# power_dist.net
KiCad netlist of a schematic drawn in EAGLE
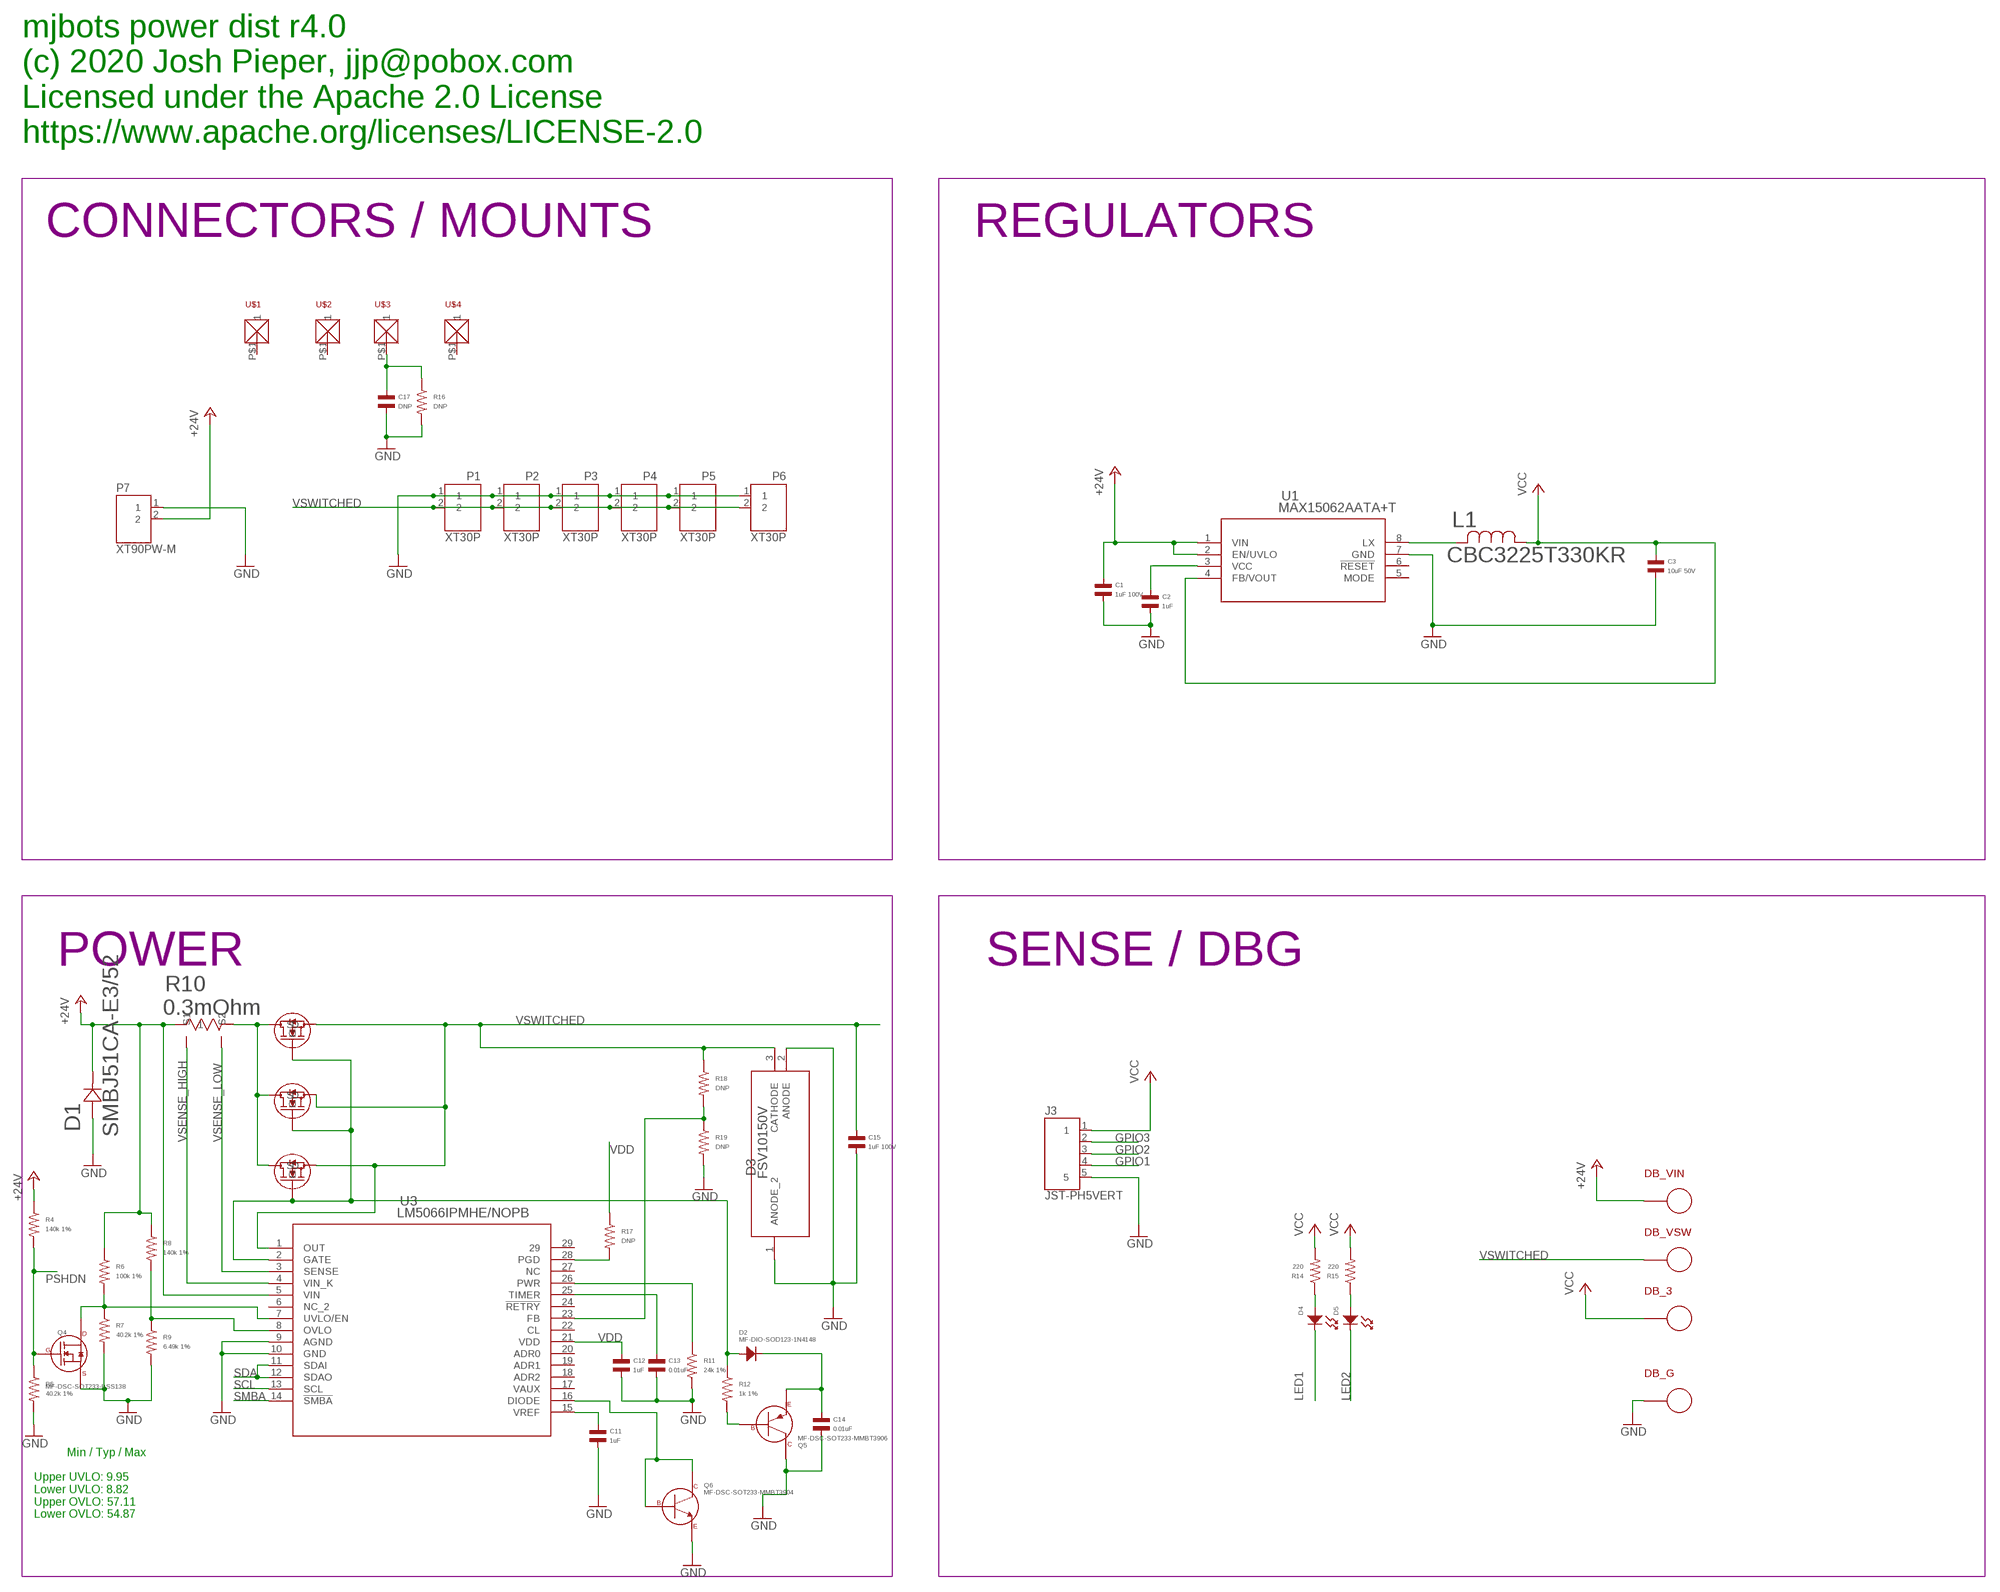
[diagram p0: schematic, sheet 1, part 1 of 2]
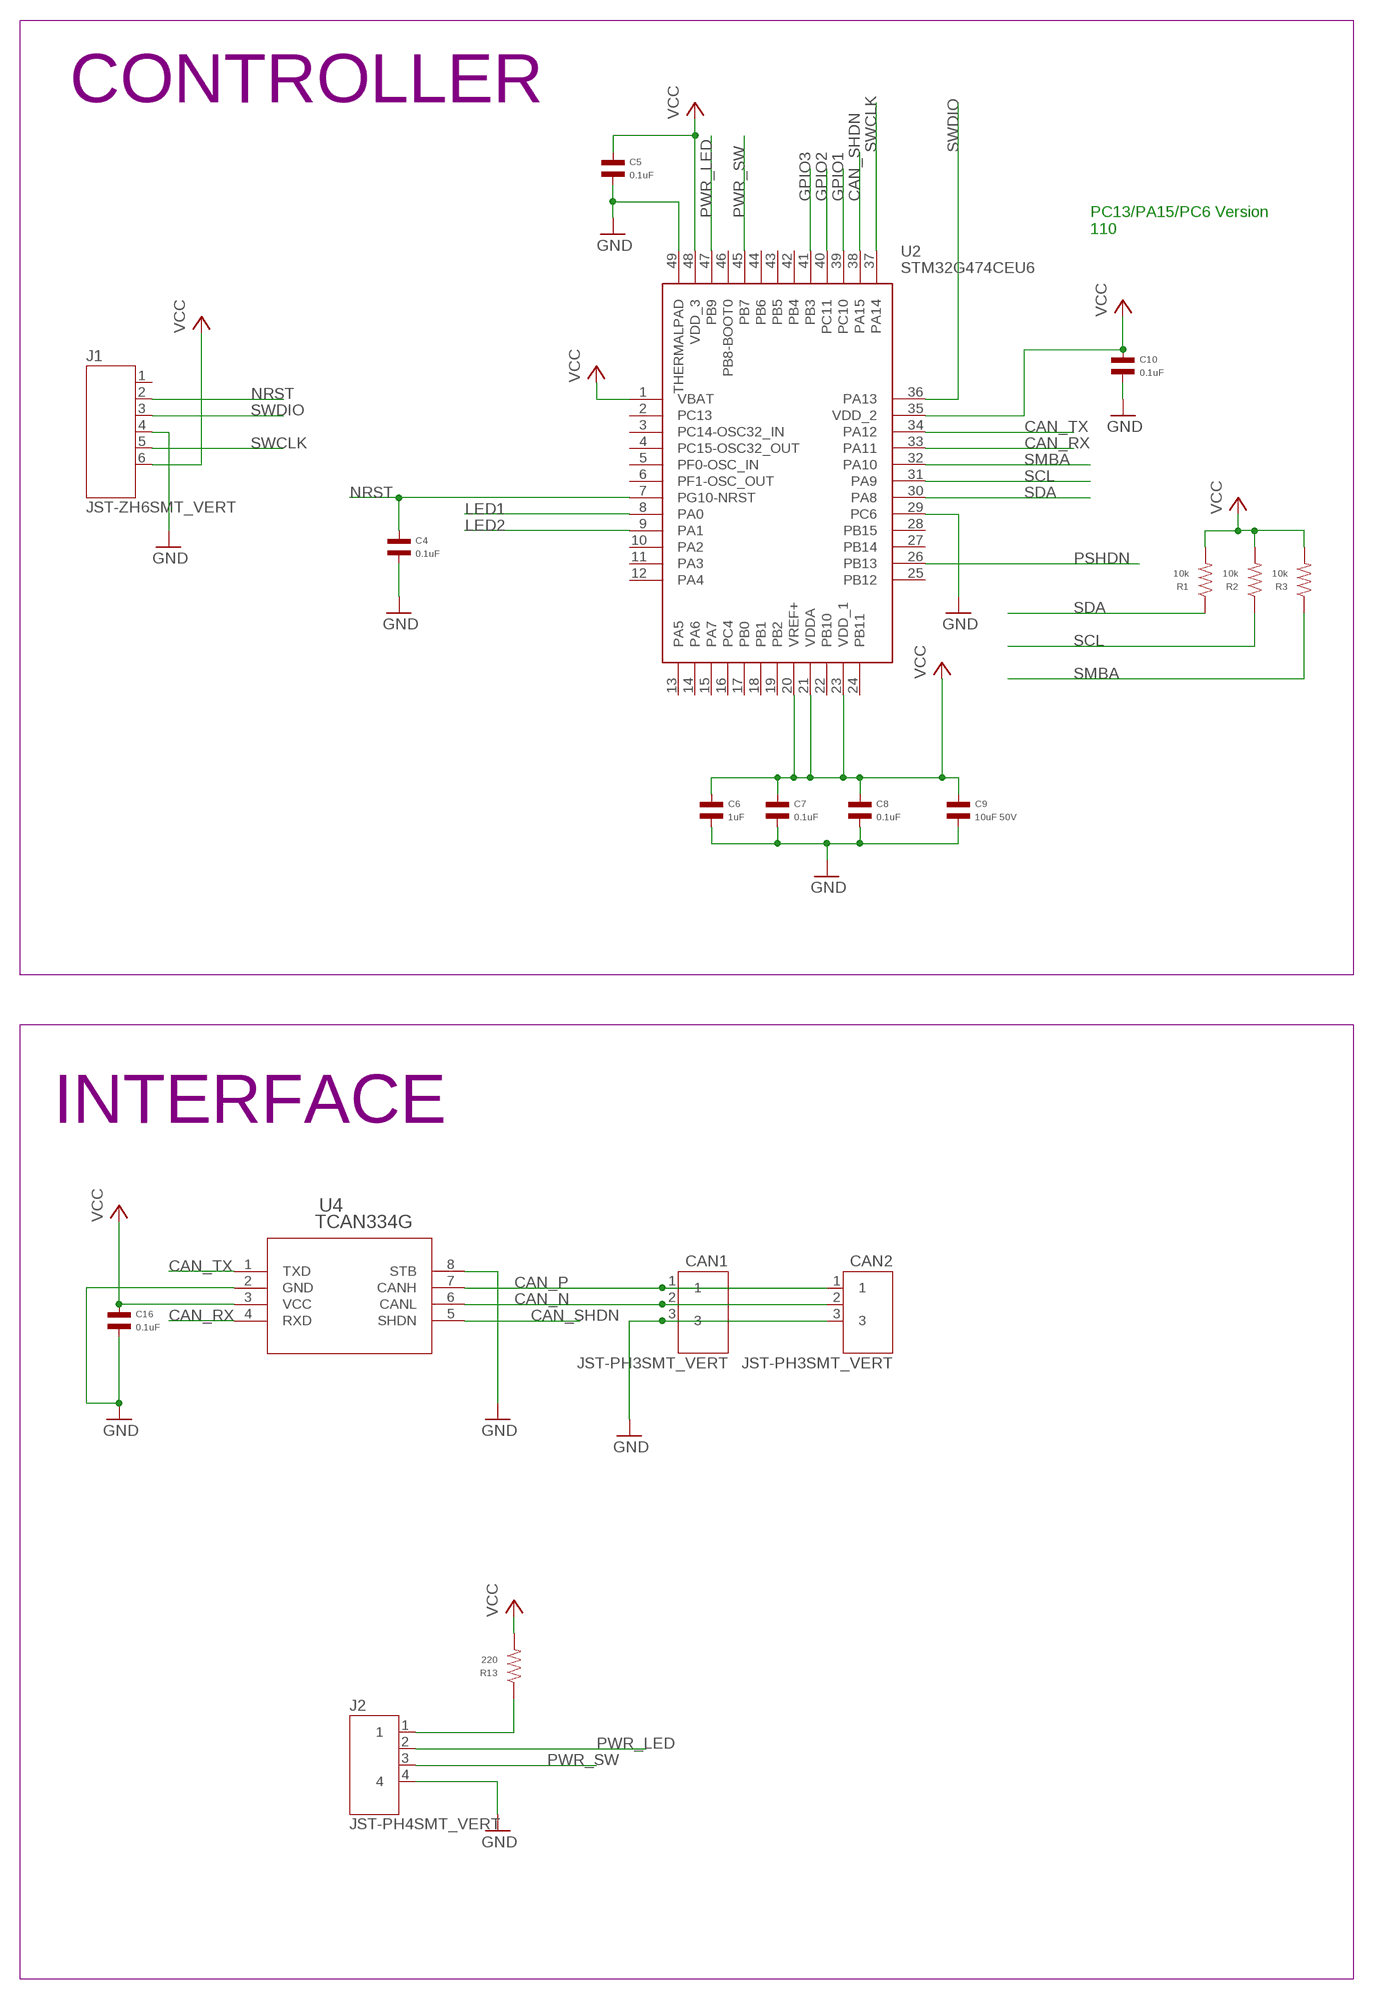
[diagram p1: schematic, sheet 1, part 2 of 2]

(export (version "E")
  (design (tool "Eeschema 10.0.6"))
  (components
    (comp (ref "C1")
      (value "1uF 100V")
      (footprint "eagle-import:C0805")
      (fields (field (name "MF") "MURATA") (field (name "MPN") "GCM21BC72A105KE36L"))
      (libsource (lib "eagle-import") (part "CAPACITOR_NP_0805"))
    )
    (comp (ref "C2")
      (value "1uF")
      (footprint "eagle-import:C0603")
      (fields (field (name "HOUSEPART") "1") (field (name "MPN") "MF-CAP-0603-1uF"))
      (libsource (lib "eagle-import") (part "CAPACITOR_NP_0603"))
    )
    (comp (ref "C3")
      (value "10uF 50V")
      (footprint "eagle-import:C1206")
      (fields (field (name "MF") "TDK") (field (name "MPN") "C3216X7R1H106K160AE"))
      (libsource (lib "eagle-import") (part "CAPACITOR_NP_1206"))
    )
    (comp (ref "C4")
      (value "0.1uF")
      (footprint "eagle-import:C0603")
      (fields (field (name "HOUSEPART") "1") (field (name "MPN") "MF-CAP-0603-0.1uF"))
      (libsource (lib "eagle-import") (part "CAPACITOR_NP_0603"))
    )
    (comp (ref "C5")
      (value "0.1uF")
      (footprint "eagle-import:C0603")
      (fields (field (name "HOUSEPART") "1") (field (name "MPN") "MF-CAP-0603-0.1uF"))
      (libsource (lib "eagle-import") (part "CAPACITOR_NP_0603"))
    )
    (comp (ref "C6")
      (value "1uF")
      (footprint "eagle-import:C0603")
      (fields (field (name "HOUSEPART") "1") (field (name "MPN") "MF-CAP-0603-1uF"))
      (libsource (lib "eagle-import") (part "CAPACITOR_NP_0603"))
    )
    (comp (ref "C7")
      (value "0.1uF")
      (footprint "eagle-import:C0603")
      (fields (field (name "HOUSEPART") "1") (field (name "MPN") "MF-CAP-0603-0.1uF"))
      (libsource (lib "eagle-import") (part "CAPACITOR_NP_0603"))
    )
    (comp (ref "C8")
      (value "0.1uF")
      (footprint "eagle-import:C0603")
      (fields (field (name "HOUSEPART") "1") (field (name "MPN") "MF-CAP-0603-0.1uF"))
      (libsource (lib "eagle-import") (part "CAPACITOR_NP_0603"))
    )
    (comp (ref "C9")
      (value "10uF 50V")
      (footprint "eagle-import:C1206")
      (fields (field (name "MF") "TDK") (field (name "MPN") "C3216X7R1H106K160AE"))
      (libsource (lib "eagle-import") (part "CAPACITOR_NP_1206"))
    )
    (comp (ref "C10")
      (value "0.1uF")
      (footprint "eagle-import:C0603")
      (fields (field (name "HOUSEPART") "1") (field (name "MPN") "MF-CAP-0603-0.1uF"))
      (libsource (lib "eagle-import") (part "CAPACITOR_NP_0603"))
    )
    (comp (ref "C11")
      (value "1uF")
      (footprint "eagle-import:C0603")
      (fields (field (name "HOUSEPART") "1") (field (name "MPN") "MF-CAP-0603-1uF"))
      (libsource (lib "eagle-import") (part "CAPACITOR_NP_0603"))
    )
    (comp (ref "C12")
      (value "1uF")
      (footprint "eagle-import:C0603")
      (fields (field (name "HOUSEPART") "1") (field (name "MPN") "MF-CAP-0603-1uF"))
      (libsource (lib "eagle-import") (part "CAPACITOR_NP_0603"))
    )
    (comp (ref "C13")
      (value "0.01uF")
      (footprint "eagle-import:C0603")
      (fields (field (name "HOUSEPART") "1") (field (name "MPN") "MF-CAP-0603-0.01uF"))
      (libsource (lib "eagle-import") (part "CAPACITOR_NP_0603"))
    )
    (comp (ref "C14")
      (value "0.01uF")
      (footprint "eagle-import:C0603")
      (fields (field (name "HOUSEPART") "1") (field (name "MPN") "MF-CAP-0603-0.01uF"))
      (libsource (lib "eagle-import") (part "CAPACITOR_NP_0603"))
    )
    (comp (ref "C15")
      (value "1uF 100V")
      (footprint "eagle-import:C0805")
      (fields (field (name "MF") "MURATA") (field (name "MPN") "GCM21BC72A105KE36L"))
      (libsource (lib "eagle-import") (part "CAPACITOR_NP_0805"))
    )
    (comp (ref "C16")
      (value "0.1uF")
      (footprint "eagle-import:C0603")
      (fields (field (name "HOUSEPART") "1") (field (name "MPN") "MF-CAP-0603-0.1uF"))
      (libsource (lib "eagle-import") (part "CAPACITOR_NP_0603"))
    )
    (comp (ref "C17")
      (value "DNP")
      (footprint "eagle-import:C0603")
      (fields (field (name "POPULATE") "0"))
      (libsource (lib "eagle-import") (part "CAPACITOR_NP_0603"))
    )
    (comp (ref "CAN1")
      (value "JST-PH3SMT_VERT")
      (footprint "eagle-import:JST_B3B_PH-SM4-TB(LF)(SN)")
      (fields (field (name "MF") "JST") (field (name "MPN") "B3B-PH-SM4-TB(LF)(SN)"))
      (libsource (lib "eagle-import") (part "JST-PH3SMT_VERT"))
    )
    (comp (ref "CAN2")
      (value "JST-PH3SMT_VERT")
      (footprint "eagle-import:JST_B3B_PH-SM4-TB(LF)(SN)")
      (fields (field (name "MF") "JST") (field (name "MPN") "B3B-PH-SM4-TB(LF)(SN)"))
      (libsource (lib "eagle-import") (part "JST-PH3SMT_VERT"))
    )
    (comp (ref "D1")
      (value "SMBJ51CA-E3/52")
      (footprint "eagle-import:DIODE_DO-214AC")
      (libsource (lib "eagle-import") (part "SMBJ51CA-E3/52"))
    )
    (comp (ref "D2")
      (value "MF-DIO-SOD123-1N4148")
      (footprint "eagle-import:SOD-123")
      (fields (field (name "HOUSEPART") "YES") (field (name "HOUSEPART_1") "1"))
      (libsource (lib "eagle-import") (part "DIODES_SOD-123_1N4148"))
    )
    (comp (ref "D3")
      (value "FSV10150V")
      (footprint "eagle-import:TO277-3L_ONS")
      (fields (field (name "COPYRIGHT") "Copyright (C) 2018 Accelerated Designs. All rights reserved"))
      (libsource (lib "eagle-import") (part "FSV10150V"))
    )
    (comp (ref "D4")
      (value "LED_SINGLE-0603")
      (footprint "eagle-import:LED0603")
      (fields
        (field (name "HOUSEPART") "NO")
        (field (name "HOUSEPART_1") "1")
        (field (name "MPN") "MF-LED-0603-RED")
      )
      (libsource (lib "eagle-import") (part "LED_SINGLE-0603"))
    )
    (comp (ref "D5")
      (value "LED_SINGLE-0603")
      (footprint "eagle-import:LED0603")
      (fields
        (field (name "HOUSEPART") "NO")
        (field (name "HOUSEPART_1") "1")
        (field (name "MPN") "MF-LED-0603-RED")
      )
      (libsource (lib "eagle-import") (part "LED_SINGLE-0603"))
    )
    (comp (ref "DB_3")
      (value "PAD24AWG_PAD")
      (footprint "eagle-import:24AWG_PAD")
      (libsource (lib "eagle-import") (part "PAD24AWG_PAD"))
    )
    (comp (ref "DB_G")
      (value "PAD24AWG_PAD")
      (footprint "eagle-import:24AWG_PAD")
      (libsource (lib "eagle-import") (part "PAD24AWG_PAD"))
    )
    (comp (ref "DB_VIN")
      (value "PAD24AWG_PAD")
      (footprint "eagle-import:24AWG_PAD")
      (libsource (lib "eagle-import") (part "PAD24AWG_PAD"))
    )
    (comp (ref "DB_VSW")
      (value "PAD24AWG_PAD")
      (footprint "eagle-import:24AWG_PAD")
      (libsource (lib "eagle-import") (part "PAD24AWG_PAD"))
    )
    (comp (ref "J1")
      (value "JST-ZH6SMT_VERT")
      (footprint "eagle-import:JST_B6B-ZR-SM4-TF(LF)(SN)")
      (fields (field (name "MF") "JST") (field (name "MPN") "B6B-ZR-SM4-TF(LF)(SN)"))
      (libsource (lib "eagle-import") (part "JST-ZH6SMT_VERT"))
    )
    (comp (ref "J2")
      (value "JST-PH4SMT_VERT")
      (footprint "eagle-import:JST_B4B_PH-SM4-TB(LF)(SN)")
      (fields (field (name "MF") "JST") (field (name "MPN") "B4B-PH-SM4-TB(LF)(SN)"))
      (libsource (lib "eagle-import") (part "JST-PH4SMT_VERT"))
    )
    (comp (ref "J3")
      (value "JST-PH5VERT")
      (footprint "eagle-import:JST_B5B_PH-SM4-TB(LF)(SN)")
      (fields (field (name "MF") "JST") (field (name "MPN") "B5B-PH-SM4-TB(LF)(SN)"))
      (libsource (lib "eagle-import") (part "JST-PH5VERT"))
    )
    (comp (ref "L1")
      (value "CBC3225T330KR")
      (footprint "eagle-import:IND_TAIYO_CBC3225_TAY")
      (libsource (lib "eagle-import") (part "CBC3225T330KR"))
    )
    (comp (ref "P1")
      (value "XT30P")
      (footprint "eagle-import:XT30P")
      (fields (field (name "MF") "AMASS") (field (name "MPN") "XT30UPB-F"))
      (libsource (lib "eagle-import") (part "XT30P"))
    )
    (comp (ref "P2")
      (value "XT30P")
      (footprint "eagle-import:XT30P")
      (fields (field (name "MF") "AMASS") (field (name "MPN") "XT30UPB-F"))
      (libsource (lib "eagle-import") (part "XT30P"))
    )
    (comp (ref "P3")
      (value "XT30P")
      (footprint "eagle-import:XT30P")
      (fields (field (name "MF") "AMASS") (field (name "MPN") "XT30UPB-F"))
      (libsource (lib "eagle-import") (part "XT30P"))
    )
    (comp (ref "P4")
      (value "XT30P")
      (footprint "eagle-import:XT30P")
      (fields (field (name "MF") "AMASS") (field (name "MPN") "XT30UPB-F"))
      (libsource (lib "eagle-import") (part "XT30P"))
    )
    (comp (ref "P5")
      (value "XT30P")
      (footprint "eagle-import:XT30P")
      (fields (field (name "MF") "AMASS") (field (name "MPN") "XT30UPB-F"))
      (libsource (lib "eagle-import") (part "XT30P"))
    )
    (comp (ref "P6")
      (value "XT30P")
      (footprint "eagle-import:XT30P")
      (fields (field (name "MF") "AMASS") (field (name "MPN") "XT30UPB-F"))
      (libsource (lib "eagle-import") (part "XT30P"))
    )
    (comp (ref "P7")
      (value "XT90PW-M")
      (footprint "eagle-import:XT90PW-M")
      (libsource (lib "eagle-import") (part "XT90PW-M"))
    )
    (comp (ref "Q1")
      (value "PSMN4R8-100BSEJ")
      (footprint "eagle-import:D2PAK_SOT404_NEX")
      (fields (field (name "COPYRIGHT") "Copyright (C) 2018 Accelerated Designs. All rights reserved"))
      (libsource (lib "eagle-import") (part "PSMN4R8-100BSEJ"))
    )
    (comp (ref "Q2")
      (value "PSMN4R8-100BSEJ")
      (footprint "eagle-import:D2PAK_SOT404_NEX")
      (fields (field (name "COPYRIGHT") "Copyright (C) 2018 Accelerated Designs. All rights reserved"))
      (libsource (lib "eagle-import") (part "PSMN4R8-100BSEJ"))
    )
    (comp (ref "Q3")
      (value "PSMN4R8-100BSEJ")
      (footprint "eagle-import:D2PAK_SOT404_NEX")
      (fields (field (name "COPYRIGHT") "Copyright (C) 2018 Accelerated Designs. All rights reserved"))
      (libsource (lib "eagle-import") (part "PSMN4R8-100BSEJ"))
    )
    (comp (ref "Q4")
      (value "MF-DSC-SOT233-BSS138")
      (footprint "eagle-import:SOT-23-3")
      (fields (field (name "HOUSEPART") "YES") (field (name "HOUSEPART_1") "1"))
      (libsource (lib "eagle-import") (part "N-CHANNEL_FET_SOT-23-3_BSS138"))
    )
    (comp (ref "Q5")
      (value "MF-DSC-SOT233-MMBT3906")
      (footprint "eagle-import:SOT-23-3")
      (fields (field (name "HOUSEPART") "YES") (field (name "HOUSEPART_1") "1"))
      (libsource (lib "eagle-import") (part "PNP_BJT_SOT-23-3_MMBT3906"))
    )
    (comp (ref "Q6")
      (value "MF-DSC-SOT233-MMBT3904")
      (footprint "eagle-import:SOT-23-3")
      (fields (field (name "HOUSEPART") "YES") (field (name "HOUSEPART_1") "1"))
      (libsource (lib "eagle-import") (part "NPN_BJT_SOT-23-3MMBT3904"))
    )
    (comp (ref "R1")
      (value "10k")
      (footprint "eagle-import:R0603")
      (fields (field (name "HOUSEPART") "1") (field (name "MPN") "MF-RES-0603-10K"))
      (libsource (lib "eagle-import") (part "RESISTOR_0603"))
    )
    (comp (ref "R2")
      (value "10k")
      (footprint "eagle-import:R0603")
      (fields (field (name "HOUSEPART") "1") (field (name "MPN") "MF-RES-0603-10K"))
      (libsource (lib "eagle-import") (part "RESISTOR_0603"))
    )
    (comp (ref "R3")
      (value "10k")
      (footprint "eagle-import:R0603")
      (fields (field (name "HOUSEPART") "1") (field (name "MPN") "MF-RES-0603-10K"))
      (libsource (lib "eagle-import") (part "RESISTOR_0603"))
    )
    (comp (ref "R4")
      (value "140k 1%")
      (footprint "eagle-import:R0603")
      (fields (field (name "MF") "YAGEO") (field (name "MPN") "RC0603FR-07140KL"))
      (libsource (lib "eagle-import") (part "RESISTOR_0603"))
    )
    (comp (ref "R5")
      (value "40.2k 1%")
      (footprint "eagle-import:R0603")
      (fields (field (name "MF") "YAGEO") (field (name "MPN") "RC0603FR-0740K2L"))
      (libsource (lib "eagle-import") (part "RESISTOR_0603"))
    )
    (comp (ref "R6")
      (value "100k 1%")
      (footprint "eagle-import:R0603")
      (fields (field (name "MF") "YAGEO") (field (name "MPN") "RC0603FR-07100KL"))
      (libsource (lib "eagle-import") (part "RESISTOR_0603"))
    )
    (comp (ref "R7")
      (value "40.2k 1%")
      (footprint "eagle-import:R0603")
      (fields (field (name "MF") "YAGEO") (field (name "MPN") "RC0603FR-0740K2L"))
      (libsource (lib "eagle-import") (part "RESISTOR_0603"))
    )
    (comp (ref "R8")
      (value "140k 1%")
      (footprint "eagle-import:R0603")
      (fields (field (name "MF") "YAGEO") (field (name "MPN") "RC0603FR-07140KL"))
      (libsource (lib "eagle-import") (part "RESISTOR_0603"))
    )
    (comp (ref "R9")
      (value "6.49k 1%")
      (footprint "eagle-import:R0603")
      (fields (field (name "MF") "YAGEO") (field (name "MPN") "RC0603FR-076K49L"))
      (libsource (lib "eagle-import") (part "RESISTOR_0603"))
    )
    (comp (ref "R10")
      (value "0.3mOhm")
      (footprint "eagle-import:SHUNT2512")
      (fields (field (name "MF") "VISHAY DALE") (field (name "MPN") "WSLF2512L3000FEA"))
      (libsource (lib "eagle-import") (part "SENSE_RESISTOR2512"))
    )
    (comp (ref "R11")
      (value "24k 1%")
      (footprint "eagle-import:R0603")
      (fields (field (name "MF") "YAGEO") (field (name "MPN") "RC0603FR-0724KL"))
      (libsource (lib "eagle-import") (part "RESISTOR_0603"))
    )
    (comp (ref "R12")
      (value "1k 1%")
      (footprint "eagle-import:R0603")
      (fields (field (name "MF") "YAGEO") (field (name "MPN") "RC0603FR-071KL"))
      (libsource (lib "eagle-import") (part "RESISTOR_0603"))
    )
    (comp (ref "R13")
      (value "220")
      (footprint "eagle-import:R0603")
      (fields (field (name "HOUSEPART") "1") (field (name "MPN") "MF-RES-0603-220"))
      (libsource (lib "eagle-import") (part "RESISTOR_0603"))
    )
    (comp (ref "R14")
      (value "220")
      (footprint "eagle-import:R0603")
      (fields (field (name "HOUSEPART") "1") (field (name "MPN") "MF-RES-0603-220"))
      (libsource (lib "eagle-import") (part "RESISTOR_0603"))
    )
    (comp (ref "R15")
      (value "220")
      (footprint "eagle-import:R0603")
      (fields (field (name "HOUSEPART") "1") (field (name "MPN") "MF-RES-0603-220"))
      (libsource (lib "eagle-import") (part "RESISTOR_0603"))
    )
    (comp (ref "R16")
      (value "DNP")
      (footprint "eagle-import:R0603")
      (fields (field (name "POPULATE") "0"))
      (libsource (lib "eagle-import") (part "RESISTOR_0603"))
    )
    (comp (ref "R17")
      (value "DNP")
      (footprint "eagle-import:R0603")
      (fields (field (name "POPULATE") "0"))
      (libsource (lib "eagle-import") (part "RESISTOR_0603"))
    )
    (comp (ref "R18")
      (value "DNP")
      (footprint "eagle-import:R0603")
      (fields (field (name "POPULATE") "0"))
      (libsource (lib "eagle-import") (part "RESISTOR_0603"))
    )
    (comp (ref "R19")
      (value "DNP")
      (footprint "eagle-import:R0603")
      (fields (field (name "POPULATE") "0"))
      (libsource (lib "eagle-import") (part "RESISTOR_0603"))
    )
    (comp (ref "U$1")
      (value "MOUNT")
      (footprint "eagle-import:M2.5MOUNT")
      (libsource (lib "eagle-import") (part "MOUNT"))
    )
    (comp (ref "U$2")
      (value "MOUNT")
      (footprint "eagle-import:M2.5MOUNT")
      (libsource (lib "eagle-import") (part "MOUNT"))
    )
    (comp (ref "U$3")
      (value "MOUNT")
      (footprint "eagle-import:M2.5MOUNT")
      (libsource (lib "eagle-import") (part "MOUNT"))
    )
    (comp (ref "U$4")
      (value "MOUNT")
      (footprint "eagle-import:M2.5MOUNT")
      (libsource (lib "eagle-import") (part "MOUNT"))
    )
    (comp (ref "U1")
      (value "MAX15062AATA+T")
      (footprint "eagle-import:21-0487A_MXM")
      (fields (field (name "COPYRIGHT") "Copyright (C) 2018 Accelerated Designs. All rights reserved"))
      (libsource (lib "eagle-import") (part "MAX15062AATA+T"))
    )
    (comp (ref "U2")
      (value "STM32G474CEU6")
      (footprint "eagle-import:QFN50P700X700X60-49N")
      (fields (field (name "MOUSER_PART_NUMBER") "511-STM32G474CEU6") (field (name "MF") "ST"))
      (libsource (lib "eagle-import") (part "STM32G474CEU6"))
    )
    (comp (ref "U3")
      (value "LM5066IPMHE/NOPB")
      (footprint "eagle-import:MXA28A_TEX")
      (fields (field (name "MANUFACTURER") "Texas Instruments") (field (name "MF") "TI"))
      (libsource (lib "eagle-import") (part "LM5066IPMHE/NOPB"))
    )
    (comp (ref "U4")
      (value "TCAN334G")
      (footprint "eagle-import:SOIC8")
      (fields (field (name "MF") "Analog") (field (name "MPN") "LTC2875IS8"))
      (libsource (lib "eagle-import") (part "TCAN334G"))
    )
  )
  (nets
    (net (code "1") (name "+24V") (class "Default")
      (node (ref "C1") (pin "P$1") (pinfunction "P$1_P$1") (pintype "passive"))
      (node (ref "D1") (pin "1") (pinfunction "1_1") (pintype "passive"))
      (node (ref "DB_VIN") (pin "P$1") (pinfunction "P$1_P$1") (pintype "bidirectional"))
      (node (ref "P7") (pin "2") (pinfunction "2_2") (pintype "passive"))
      (node (ref "R10") (pin "1") (pinfunction "1_1") (pintype "passive"))
      (node (ref "R4") (pin "P$1") (pinfunction "P$1_P$1") (pintype "passive"))
      (node (ref "R6") (pin "P$1") (pinfunction "P$1_P$1") (pintype "passive"))
      (node (ref "R8") (pin "P$1") (pinfunction "P$1_P$1") (pintype "passive"))
      (node (ref "U1") (pin "1") (pinfunction "VIN_1") (pintype "input"))
      (node (ref "U1") (pin "2") (pinfunction "EN/UVLO_2") (pintype "input"))
      (node (ref "U3") (pin "5") (pinfunction "VIN_5") (pintype "input"))
    )
    (net (code "2") (name "/CAN_N") (class "Default")
      (node (ref "CAN1") (pin "2") (pinfunction "2_2") (pintype "passive"))
      (node (ref "CAN2") (pin "2") (pinfunction "2_2") (pintype "passive"))
      (node (ref "U4") (pin "6") (pinfunction "CANL_6") (pintype "bidirectional"))
    )
    (net (code "3") (name "/CAN_P") (class "Default")
      (node (ref "CAN1") (pin "1") (pinfunction "1_1") (pintype "passive"))
      (node (ref "CAN2") (pin "1") (pinfunction "1_1") (pintype "passive"))
      (node (ref "U4") (pin "7") (pinfunction "CANH_7") (pintype "bidirectional"))
    )
    (net (code "4") (name "/CAN_RX") (class "Default")
      (node (ref "U2") (pin "33") (pinfunction "PA11_33") (pintype "bidirectional"))
      (node (ref "U4") (pin "4") (pinfunction "RXD_4") (pintype "output"))
    )
    (net (code "5") (name "/CAN_SHDN") (class "Default")
      (node (ref "U2") (pin "38") (pinfunction "PA15_38") (pintype "bidirectional"))
      (node (ref "U4") (pin "5") (pinfunction "SHDN_5") (pintype "input"))
    )
    (net (code "6") (name "/CAN_TX") (class "Default")
      (node (ref "U2") (pin "34") (pinfunction "PA12_34") (pintype "bidirectional"))
      (node (ref "U4") (pin "1") (pinfunction "TXD_1") (pintype "input"))
    )
    (net (code "7") (name "/GPIO1") (class "Default")
      (node (ref "J3") (pin "4") (pinfunction "4_4") (pintype "passive"))
      (node (ref "U2") (pin "39") (pinfunction "PC10_39") (pintype "bidirectional"))
    )
    (net (code "8") (name "/GPIO2") (class "Default")
      (node (ref "J3") (pin "3") (pinfunction "3_3") (pintype "passive"))
      (node (ref "U2") (pin "40") (pinfunction "PC11_40") (pintype "bidirectional"))
    )
    (net (code "9") (name "/GPIO3") (class "Default")
      (node (ref "J3") (pin "2") (pinfunction "2_2") (pintype "passive"))
      (node (ref "U2") (pin "41") (pinfunction "PB3_41") (pintype "bidirectional"))
    )
    (net (code "10") (name "/LED1") (class "Default")
      (node (ref "D4") (pin "CATHODE") (pinfunction "CATHODE_CATHODE") (pintype "power_in"))
      (node (ref "U2") (pin "8") (pinfunction "PA0_8") (pintype "bidirectional"))
    )
    (net (code "11") (name "/LED2") (class "Default")
      (node (ref "D5") (pin "CATHODE") (pinfunction "CATHODE_CATHODE") (pintype "power_in"))
      (node (ref "U2") (pin "9") (pinfunction "PA1_9") (pintype "bidirectional"))
    )
    (net (code "12") (name "/NRST") (class "Default")
      (node (ref "C4") (pin "P$1") (pinfunction "P$1_P$1") (pintype "passive"))
      (node (ref "J1") (pin "2") (pinfunction "2_2") (pintype "passive"))
      (node (ref "U2") (pin "7") (pinfunction "PG10-NRST_7") (pintype "bidirectional"))
    )
    (net (code "13") (name "/PSHDN") (class "Default")
      (node (ref "Q4") (pin "P$1") (pinfunction "GATE_P$1") (pintype "bidirectional"))
      (node (ref "R4") (pin "P$2") (pinfunction "P$2_P$2") (pintype "passive"))
      (node (ref "R5") (pin "P$1") (pinfunction "P$1_P$1") (pintype "passive"))
      (node (ref "U2") (pin "26") (pinfunction "PB13_26") (pintype "bidirectional"))
    )
    (net (code "14") (name "/PWR_LED") (class "Default")
      (node (ref "J2") (pin "2") (pinfunction "2_2") (pintype "passive"))
      (node (ref "U2") (pin "47") (pinfunction "PB9_47") (pintype "bidirectional"))
    )
    (net (code "15") (name "/PWR_SW") (class "Default")
      (node (ref "J2") (pin "3") (pinfunction "3_3") (pintype "passive"))
      (node (ref "U2") (pin "45") (pinfunction "PB7_45") (pintype "bidirectional"))
    )
    (net (code "16") (name "/SCL") (class "Default")
      (node (ref "R2") (pin "P$1") (pinfunction "P$1_P$1") (pintype "passive"))
      (node (ref "U2") (pin "31") (pinfunction "PA9_31") (pintype "bidirectional"))
      (node (ref "U3") (pin "13") (pinfunction "SCL_13") (pintype "passive"))
    )
    (net (code "17") (name "/SDA") (class "Default")
      (node (ref "R1") (pin "P$1") (pinfunction "P$1_P$1") (pintype "passive"))
      (node (ref "U2") (pin "30") (pinfunction "PA8_30") (pintype "bidirectional"))
      (node (ref "U3") (pin "11") (pinfunction "SDAI_11") (pintype "input"))
      (node (ref "U3") (pin "12") (pinfunction "SDAO_12") (pintype "output"))
    )
    (net (code "18") (name "/SMBA") (class "Default")
      (node (ref "R3") (pin "P$1") (pinfunction "P$1_P$1") (pintype "passive"))
      (node (ref "U2") (pin "32") (pinfunction "PA10_32") (pintype "bidirectional"))
      (node (ref "U3") (pin "14") (pinfunction "~{SMBA}_14") (pintype "passive"))
    )
    (net (code "19") (name "/SWCLK") (class "Default")
      (node (ref "J1") (pin "5") (pinfunction "5_5") (pintype "passive"))
      (node (ref "U2") (pin "37") (pinfunction "PA14_37") (pintype "bidirectional"))
    )
    (net (code "20") (name "/SWDIO") (class "Default")
      (node (ref "J1") (pin "3") (pinfunction "3_3") (pintype "passive"))
      (node (ref "U2") (pin "36") (pinfunction "PA13_36") (pintype "bidirectional"))
    )
    (net (code "21") (name "/VDD") (class "Default")
      (node (ref "C12") (pin "P$1") (pinfunction "P$1_P$1") (pintype "passive"))
      (node (ref "R17") (pin "P$1") (pinfunction "P$1_P$1") (pintype "passive"))
      (node (ref "U3") (pin "21") (pinfunction "VDD_21") (pintype "power_in"))
    )
    (net (code "22") (name "/VSENSE_HIGH") (class "Default")
      (node (ref "R10") (pin "3") (pinfunction "S1_3") (pintype "passive"))
      (node (ref "U3") (pin "4") (pinfunction "VIN_K_4") (pintype "input"))
    )
    (net (code "23") (name "/VSENSE_LOW") (class "Default")
      (node (ref "R10") (pin "4") (pinfunction "S2_4") (pintype "passive"))
      (node (ref "U3") (pin "3") (pinfunction "SENSE_3") (pintype "input"))
    )
    (net (code "24") (name "/VSWITCHED") (class "Default")
      (node (ref "C15") (pin "P$1") (pinfunction "P$1_P$1") (pintype "passive"))
      (node (ref "D3") (pin "3") (pinfunction "CATHODE_3") (pintype "passive"))
      (node (ref "DB_VSW") (pin "P$1") (pinfunction "P$1_P$1") (pintype "bidirectional"))
      (node (ref "P1") (pin "2") (pinfunction "2_2") (pintype "passive"))
      (node (ref "P2") (pin "2") (pinfunction "2_2") (pintype "passive"))
      (node (ref "P3") (pin "2") (pinfunction "2_2") (pintype "passive"))
      (node (ref "P4") (pin "2") (pinfunction "2_2") (pintype "passive"))
      (node (ref "P5") (pin "2") (pinfunction "2_2") (pintype "passive"))
      (node (ref "P6") (pin "2") (pinfunction "2_2") (pintype "passive"))
      (node (ref "Q1") (pin "3") (pinfunction "S_3") (pintype "passive"))
      (node (ref "Q2") (pin "3") (pinfunction "S_3") (pintype "passive"))
      (node (ref "Q3") (pin "3") (pinfunction "S_3") (pintype "passive"))
      (node (ref "R18") (pin "P$1") (pinfunction "P$1_P$1") (pintype "passive"))
      (node (ref "U3") (pin "1") (pinfunction "OUT_1") (pintype "output"))
    )
    (net (code "25") (name "GND") (class "Default")
      (node (ref "C1") (pin "P$2") (pinfunction "P$2_P$2") (pintype "passive"))
      (node (ref "C10") (pin "P$2") (pinfunction "P$2_P$2") (pintype "passive"))
      (node (ref "C11") (pin "P$2") (pinfunction "P$2_P$2") (pintype "passive"))
      (node (ref "C12") (pin "P$2") (pinfunction "P$2_P$2") (pintype "passive"))
      (node (ref "C13") (pin "P$2") (pinfunction "P$2_P$2") (pintype "passive"))
      (node (ref "C14") (pin "P$2") (pinfunction "P$2_P$2") (pintype "passive"))
      (node (ref "C15") (pin "P$2") (pinfunction "P$2_P$2") (pintype "passive"))
      (node (ref "C16") (pin "P$2") (pinfunction "P$2_P$2") (pintype "passive"))
      (node (ref "C17") (pin "P$2") (pinfunction "P$2_P$2") (pintype "passive"))
      (node (ref "C2") (pin "P$2") (pinfunction "P$2_P$2") (pintype "passive"))
      (node (ref "C3") (pin "P$2") (pinfunction "P$2_P$2") (pintype "passive"))
      (node (ref "C4") (pin "P$2") (pinfunction "P$2_P$2") (pintype "passive"))
      (node (ref "C5") (pin "P$2") (pinfunction "P$2_P$2") (pintype "passive"))
      (node (ref "C6") (pin "P$2") (pinfunction "P$2_P$2") (pintype "passive"))
      (node (ref "C7") (pin "P$2") (pinfunction "P$2_P$2") (pintype "passive"))
      (node (ref "C8") (pin "P$2") (pinfunction "P$2_P$2") (pintype "passive"))
      (node (ref "C9") (pin "P$2") (pinfunction "P$2_P$2") (pintype "passive"))
      (node (ref "CAN1") (pin "3") (pinfunction "3_3") (pintype "passive"))
      (node (ref "CAN2") (pin "3") (pinfunction "3_3") (pintype "passive"))
      (node (ref "D1") (pin "2") (pinfunction "2_2") (pintype "passive"))
      (node (ref "D3") (pin "1") (pinfunction "ANODE_2_1") (pintype "passive"))
      (node (ref "D3") (pin "2") (pinfunction "ANODE_2") (pintype "passive"))
      (node (ref "DB_G") (pin "P$1") (pinfunction "P$1_P$1") (pintype "bidirectional"))
      (node (ref "J1") (pin "4") (pinfunction "4_4") (pintype "passive"))
      (node (ref "J2") (pin "4") (pinfunction "4_4") (pintype "passive"))
      (node (ref "J3") (pin "5") (pinfunction "5_5") (pintype "passive"))
      (node (ref "P1") (pin "1") (pinfunction "1_1") (pintype "passive"))
      (node (ref "P2") (pin "1") (pinfunction "1_1") (pintype "passive"))
      (node (ref "P3") (pin "1") (pinfunction "1_1") (pintype "passive"))
      (node (ref "P4") (pin "1") (pinfunction "1_1") (pintype "passive"))
      (node (ref "P5") (pin "1") (pinfunction "1_1") (pintype "passive"))
      (node (ref "P6") (pin "1") (pinfunction "1_1") (pintype "passive"))
      (node (ref "P7") (pin "1") (pinfunction "1_1") (pintype "passive"))
      (node (ref "Q4") (pin "P$2") (pinfunction "SOURCE_P$2") (pintype "bidirectional"))
      (node (ref "Q5") (pin "P$3") (pinfunction "COLLECTOR_P$3") (pintype "bidirectional"))
      (node (ref "Q6") (pin "P$2") (pinfunction "EMITTER_P$2") (pintype "bidirectional"))
      (node (ref "R11") (pin "P$2") (pinfunction "P$2_P$2") (pintype "passive"))
      (node (ref "R16") (pin "P$2") (pinfunction "P$2_P$2") (pintype "passive"))
      (node (ref "R19") (pin "P$2") (pinfunction "P$2_P$2") (pintype "passive"))
      (node (ref "R5") (pin "P$2") (pinfunction "P$2_P$2") (pintype "passive"))
      (node (ref "R7") (pin "P$2") (pinfunction "P$2_P$2") (pintype "passive"))
      (node (ref "R9") (pin "P$2") (pinfunction "P$2_P$2") (pintype "passive"))
      (node (ref "U1") (pin "7") (pinfunction "GND_7") (pintype "power_in"))
      (node (ref "U2") (pin "29") (pinfunction "PC6_29") (pintype "bidirectional"))
      (node (ref "U2") (pin "49") (pinfunction "THERMALPAD_49") (pintype "bidirectional"))
      (node (ref "U3") (pin "10") (pinfunction "GND_10") (pintype "power_in"))
      (node (ref "U3") (pin "9") (pinfunction "AGND_9") (pintype "power_in"))
      (node (ref "U4") (pin "2") (pinfunction "GND_2") (pintype "power_in"))
      (node (ref "U4") (pin "8") (pinfunction "STB_8") (pintype "input"))
    )
    (net (code "26") (name "Net-(D4-PadANODE)") (class "Default")
      (node (ref "D4") (pin "ANODE") (pinfunction "ANODE_ANODE") (pintype "power_in"))
      (node (ref "R14") (pin "P$1") (pinfunction "P$1_P$1") (pintype "passive"))
    )
    (net (code "27") (name "Net-(D5-PadANODE)") (class "Default")
      (node (ref "D5") (pin "ANODE") (pinfunction "ANODE_ANODE") (pintype "power_in"))
      (node (ref "R15") (pin "P$1") (pinfunction "P$1_P$1") (pintype "passive"))
    )
    (net (code "28") (name "Net-(J2-Pad1)") (class "Default")
      (node (ref "J2") (pin "1") (pinfunction "1_1") (pintype "passive"))
      (node (ref "R13") (pin "P$1") (pinfunction "P$1_P$1") (pintype "passive"))
    )
    (net (code "29") (name "Net-(Q1-D)") (class "Default")
      (node (ref "Q1") (pin "2") (pinfunction "D_2") (pintype "passive"))
      (node (ref "Q2") (pin "2") (pinfunction "D_2") (pintype "passive"))
      (node (ref "Q3") (pin "2") (pinfunction "D_2") (pintype "passive"))
      (node (ref "R10") (pin "2") (pinfunction "2_2") (pintype "passive"))
    )
    (net (code "30") (name "Net-(Q1-G)") (class "Default")
      (node (ref "D2") (pin "ANODE") (pinfunction "ANODE_ANODE") (pintype "bidirectional"))
      (node (ref "Q1") (pin "1") (pinfunction "G_1") (pintype "passive"))
      (node (ref "Q2") (pin "1") (pinfunction "G_1") (pintype "passive"))
      (node (ref "Q3") (pin "1") (pinfunction "G_1") (pintype "passive"))
      (node (ref "R12") (pin "P$1") (pinfunction "P$1_P$1") (pintype "passive"))
      (node (ref "U3") (pin "2") (pinfunction "GATE_2") (pintype "output"))
    )
    (net (code "31") (name "Net-(Q4-DRAIN)") (class "Default")
      (node (ref "Q4") (pin "P$3") (pinfunction "DRAIN_P$3") (pintype "bidirectional"))
      (node (ref "R6") (pin "P$2") (pinfunction "P$2_P$2") (pintype "passive"))
      (node (ref "R7") (pin "P$1") (pinfunction "P$1_P$1") (pintype "passive"))
      (node (ref "U3") (pin "7") (pinfunction "UVLO/EN_7") (pintype "passive"))
    )
    (net (code "32") (name "Net-(Q5-BASE)") (class "Default")
      (node (ref "Q5") (pin "P$1") (pinfunction "BASE_P$1") (pintype "bidirectional"))
      (node (ref "R12") (pin "P$2") (pinfunction "P$2_P$2") (pintype "passive"))
    )
    (net (code "33") (name "Net-(Q5-EMITTER)") (class "Default")
      (node (ref "C14") (pin "P$1") (pinfunction "P$1_P$1") (pintype "passive"))
      (node (ref "D2") (pin "CATHODE") (pinfunction "CATHODE_CATHODE") (pintype "bidirectional"))
      (node (ref "Q5") (pin "P$2") (pinfunction "EMITTER_P$2") (pintype "bidirectional"))
    )
    (net (code "34") (name "Net-(Q6-BASE)") (class "Default")
      (node (ref "Q6") (pin "P$1") (pinfunction "BASE_P$1") (pintype "bidirectional"))
      (node (ref "Q6") (pin "P$3") (pinfunction "COLLECTOR_P$3") (pintype "bidirectional"))
      (node (ref "U3") (pin "16") (pinfunction "DIODE_16") (pintype "passive"))
    )
    (net (code "35") (name "Net-(U$3-1)") (class "Default")
      (node (ref "C17") (pin "P$1") (pinfunction "P$1_P$1") (pintype "passive"))
      (node (ref "R16") (pin "P$1") (pinfunction "P$1_P$1") (pintype "passive"))
      (node (ref "U$3") (pin "P$1") (pinfunction "1_P$1") (pintype "passive"))
    )
    (net (code "36") (name "Net-(U1-LX)") (class "Default")
      (node (ref "L1") (pin "2") (pinfunction "2_2") (pintype "passive"))
      (node (ref "U1") (pin "8") (pinfunction "LX_8") (pintype "passive"))
    )
    (net (code "37") (name "Net-(U1-VCC)") (class "Default")
      (node (ref "C2") (pin "P$1") (pinfunction "P$1_P$1") (pintype "passive"))
      (node (ref "U1") (pin "3") (pinfunction "VCC_3") (pintype "power_in"))
    )
    (net (code "38") (name "Net-(U3-FB)") (class "Default")
      (node (ref "R18") (pin "P$2") (pinfunction "P$2_P$2") (pintype "passive"))
      (node (ref "R19") (pin "P$1") (pinfunction "P$1_P$1") (pintype "passive"))
      (node (ref "U3") (pin "23") (pinfunction "FB_23") (pintype "output"))
    )
    (net (code "39") (name "Net-(U3-OVLO)") (class "Default")
      (node (ref "R8") (pin "P$2") (pinfunction "P$2_P$2") (pintype "passive"))
      (node (ref "R9") (pin "P$1") (pinfunction "P$1_P$1") (pintype "passive"))
      (node (ref "U3") (pin "8") (pinfunction "OVLO_8") (pintype "input"))
    )
    (net (code "40") (name "Net-(U3-PGD)") (class "Default")
      (node (ref "R17") (pin "P$2") (pinfunction "P$2_P$2") (pintype "passive"))
      (node (ref "U3") (pin "28") (pinfunction "PGD_28") (pintype "power_in"))
    )
    (net (code "41") (name "Net-(U3-PWR)") (class "Default")
      (node (ref "R11") (pin "P$1") (pinfunction "P$1_P$1") (pintype "passive"))
      (node (ref "U3") (pin "26") (pinfunction "PWR_26") (pintype "power_in"))
    )
    (net (code "42") (name "Net-(U3-TIMER)") (class "Default")
      (node (ref "C13") (pin "P$1") (pinfunction "P$1_P$1") (pintype "passive"))
      (node (ref "U3") (pin "25") (pinfunction "TIMER_25") (pintype "passive"))
    )
    (net (code "43") (name "Net-(U3-VREF)") (class "Default")
      (node (ref "C11") (pin "P$1") (pinfunction "P$1_P$1") (pintype "passive"))
      (node (ref "U3") (pin "15") (pinfunction "VREF_15") (pintype "passive"))
    )
    (net (code "44") (name "VCC") (class "Default")
      (node (ref "C10") (pin "P$1") (pinfunction "P$1_P$1") (pintype "passive"))
      (node (ref "C16") (pin "P$1") (pinfunction "P$1_P$1") (pintype "passive"))
      (node (ref "C3") (pin "P$1") (pinfunction "P$1_P$1") (pintype "passive"))
      (node (ref "C5") (pin "P$1") (pinfunction "P$1_P$1") (pintype "passive"))
      (node (ref "C6") (pin "P$1") (pinfunction "P$1_P$1") (pintype "passive"))
      (node (ref "C7") (pin "P$1") (pinfunction "P$1_P$1") (pintype "passive"))
      (node (ref "C8") (pin "P$1") (pinfunction "P$1_P$1") (pintype "passive"))
      (node (ref "C9") (pin "P$1") (pinfunction "P$1_P$1") (pintype "passive"))
      (node (ref "DB_3") (pin "P$1") (pinfunction "P$1_P$1") (pintype "bidirectional"))
      (node (ref "J1") (pin "6") (pinfunction "6_6") (pintype "passive"))
      (node (ref "J3") (pin "1") (pinfunction "1_1") (pintype "passive"))
      (node (ref "L1") (pin "1") (pinfunction "1_1") (pintype "passive"))
      (node (ref "R1") (pin "P$2") (pinfunction "P$2_P$2") (pintype "passive"))
      (node (ref "R13") (pin "P$2") (pinfunction "P$2_P$2") (pintype "passive"))
      (node (ref "R14") (pin "P$2") (pinfunction "P$2_P$2") (pintype "passive"))
      (node (ref "R15") (pin "P$2") (pinfunction "P$2_P$2") (pintype "passive"))
      (node (ref "R2") (pin "P$2") (pinfunction "P$2_P$2") (pintype "passive"))
      (node (ref "R3") (pin "P$2") (pinfunction "P$2_P$2") (pintype "passive"))
      (node (ref "U1") (pin "4") (pinfunction "FB/VOUT_4") (pintype "bidirectional"))
      (node (ref "U2") (pin "1") (pinfunction "VBAT_1") (pintype "bidirectional"))
      (node (ref "U2") (pin "20") (pinfunction "VREF+_20") (pintype "bidirectional"))
      (node (ref "U2") (pin "21") (pinfunction "VDDA_21") (pintype "bidirectional"))
      (node (ref "U2") (pin "23") (pinfunction "VDD_1_23") (pintype "bidirectional"))
      (node (ref "U2") (pin "35") (pinfunction "VDD_2_35") (pintype "bidirectional"))
      (node (ref "U2") (pin "48") (pinfunction "VDD_3_48") (pintype "bidirectional"))
      (node (ref "U4") (pin "3") (pinfunction "VCC_3") (pintype "power_in"))
    )
    (net (code "45") (name "unconnected-(J1-Pad1)") (class "Default")
      (node (ref "J1") (pin "1") (pinfunction "1_1") (pintype "passive"))
    )
    (net (code "46") (name "unconnected-(U$1-1-PadP$1)") (class "Default")
      (node (ref "U$1") (pin "P$1") (pinfunction "1_P$1") (pintype "passive"))
    )
    (net (code "47") (name "unconnected-(U$2-1-PadP$1)") (class "Default")
      (node (ref "U$2") (pin "P$1") (pinfunction "1_P$1") (pintype "passive"))
    )
    (net (code "48") (name "unconnected-(U$4-1-PadP$1)") (class "Default")
      (node (ref "U$4") (pin "P$1") (pinfunction "1_P$1") (pintype "passive"))
    )
    (net (code "49") (name "unconnected-(U1-MODE-Pad5)") (class "Default")
      (node (ref "U1") (pin "5") (pinfunction "MODE_5") (pintype "input"))
    )
    (net (code "50") (name "unconnected-(U1-~{RESET}-Pad6)") (class "Default")
      (node (ref "U1") (pin "6") (pinfunction "~{RESET}_6") (pintype "output"))
    )
    (net (code "51") (name "unconnected-(U2-PA2-Pad10)") (class "Default")
      (node (ref "U2") (pin "10") (pinfunction "PA2_10") (pintype "bidirectional"))
    )
    (net (code "52") (name "unconnected-(U2-PA3-Pad11)") (class "Default")
      (node (ref "U2") (pin "11") (pinfunction "PA3_11") (pintype "bidirectional"))
    )
    (net (code "53") (name "unconnected-(U2-PA4-Pad12)") (class "Default")
      (node (ref "U2") (pin "12") (pinfunction "PA4_12") (pintype "bidirectional"))
    )
    (net (code "54") (name "unconnected-(U2-PA5-Pad13)") (class "Default")
      (node (ref "U2") (pin "13") (pinfunction "PA5_13") (pintype "bidirectional"))
    )
    (net (code "55") (name "unconnected-(U2-PA6-Pad14)") (class "Default")
      (node (ref "U2") (pin "14") (pinfunction "PA6_14") (pintype "bidirectional"))
    )
    (net (code "56") (name "unconnected-(U2-PA7-Pad15)") (class "Default")
      (node (ref "U2") (pin "15") (pinfunction "PA7_15") (pintype "bidirectional"))
    )
    (net (code "57") (name "unconnected-(U2-PB0-Pad17)") (class "Default")
      (node (ref "U2") (pin "17") (pinfunction "PB0_17") (pintype "bidirectional"))
    )
    (net (code "58") (name "unconnected-(U2-PB1-Pad18)") (class "Default")
      (node (ref "U2") (pin "18") (pinfunction "PB1_18") (pintype "bidirectional"))
    )
    (net (code "59") (name "unconnected-(U2-PB2-Pad19)") (class "Default")
      (node (ref "U2") (pin "19") (pinfunction "PB2_19") (pintype "bidirectional"))
    )
    (net (code "60") (name "unconnected-(U2-PB4-Pad42)") (class "Default")
      (node (ref "U2") (pin "42") (pinfunction "PB4_42") (pintype "bidirectional"))
    )
    (net (code "61") (name "unconnected-(U2-PB5-Pad43)") (class "Default")
      (node (ref "U2") (pin "43") (pinfunction "PB5_43") (pintype "bidirectional"))
    )
    (net (code "62") (name "unconnected-(U2-PB6-Pad44)") (class "Default")
      (node (ref "U2") (pin "44") (pinfunction "PB6_44") (pintype "bidirectional"))
    )
    (net (code "63") (name "unconnected-(U2-PB8-BOOT0-Pad46)") (class "Default")
      (node (ref "U2") (pin "46") (pinfunction "PB8-BOOT0_46") (pintype "bidirectional"))
    )
    (net (code "64") (name "unconnected-(U2-PB10-Pad22)") (class "Default")
      (node (ref "U2") (pin "22") (pinfunction "PB10_22") (pintype "bidirectional"))
    )
    (net (code "65") (name "unconnected-(U2-PB11-Pad24)") (class "Default")
      (node (ref "U2") (pin "24") (pinfunction "PB11_24") (pintype "bidirectional"))
    )
    (net (code "66") (name "unconnected-(U2-PB12-Pad25)") (class "Default")
      (node (ref "U2") (pin "25") (pinfunction "PB12_25") (pintype "bidirectional"))
    )
    (net (code "67") (name "unconnected-(U2-PB14-Pad27)") (class "Default")
      (node (ref "U2") (pin "27") (pinfunction "PB14_27") (pintype "bidirectional"))
    )
    (net (code "68") (name "unconnected-(U2-PB15-Pad28)") (class "Default")
      (node (ref "U2") (pin "28") (pinfunction "PB15_28") (pintype "bidirectional"))
    )
    (net (code "69") (name "unconnected-(U2-PC4-Pad16)") (class "Default")
      (node (ref "U2") (pin "16") (pinfunction "PC4_16") (pintype "bidirectional"))
    )
    (net (code "70") (name "unconnected-(U2-PC13-Pad2)") (class "Default")
      (node (ref "U2") (pin "2") (pinfunction "PC13_2") (pintype "bidirectional"))
    )
    (net (code "71") (name "unconnected-(U2-PC14-OSC32_IN-Pad3)") (class "Default")
      (node (ref "U2") (pin "3") (pinfunction "PC14-OSC32_IN_3") (pintype "bidirectional"))
    )
    (net (code "72") (name "unconnected-(U2-PC15-OSC32_OUT-Pad4)") (class "Default")
      (node (ref "U2") (pin "4") (pinfunction "PC15-OSC32_OUT_4") (pintype "bidirectional"))
    )
    (net (code "73") (name "unconnected-(U2-PF0-OSC_IN-Pad5)") (class "Default")
      (node (ref "U2") (pin "5") (pinfunction "PF0-OSC_IN_5") (pintype "bidirectional"))
    )
    (net (code "74") (name "unconnected-(U2-PF1-OSC_OUT-Pad6)") (class "Default")
      (node (ref "U2") (pin "6") (pinfunction "PF1-OSC_OUT_6") (pintype "bidirectional"))
    )
    (net (code "75") (name "unconnected-(U3-ADR0-Pad20)") (class "Default")
      (node (ref "U3") (pin "20") (pinfunction "ADR0_20") (pintype "passive"))
    )
    (net (code "76") (name "unconnected-(U3-ADR1-Pad19)") (class "Default")
      (node (ref "U3") (pin "19") (pinfunction "ADR1_19") (pintype "passive"))
    )
    (net (code "77") (name "unconnected-(U3-ADR2-Pad18)") (class "Default")
      (node (ref "U3") (pin "18") (pinfunction "ADR2_18") (pintype "passive"))
    )
    (net (code "78") (name "unconnected-(U3-CL-Pad22)") (class "Default")
      (node (ref "U3") (pin "22") (pinfunction "CL_22") (pintype "passive"))
    )
    (net (code "79") (name "unconnected-(U3-NC-Pad27)") (class "Default")
      (node (ref "U3") (pin "27") (pinfunction "NC_27") (pintype "no_connect"))
    )
    (net (code "80") (name "unconnected-(U3-NC_2-Pad6)") (class "Default")
      (node (ref "U3") (pin "6") (pinfunction "NC_2_6") (pintype "no_connect"))
    )
    (net (code "81") (name "unconnected-(U3-Pad29)") (class "Default")
      (node (ref "U3") (pin "29") (pinfunction "29_29") (pintype "passive"))
    )
    (net (code "82") (name "unconnected-(U3-VAUX-Pad17)") (class "Default")
      (node (ref "U3") (pin "17") (pinfunction "VAUX_17") (pintype "input"))
    )
    (net (code "83") (name "unconnected-(U3-~{RETRY}-Pad24)") (class "Default")
      (node (ref "U3") (pin "24") (pinfunction "~{RETRY}_24") (pintype "input"))
    )
  )
)
